# arduinoshield.net
KiCad netlist of a schematic drawn in Altium Designer
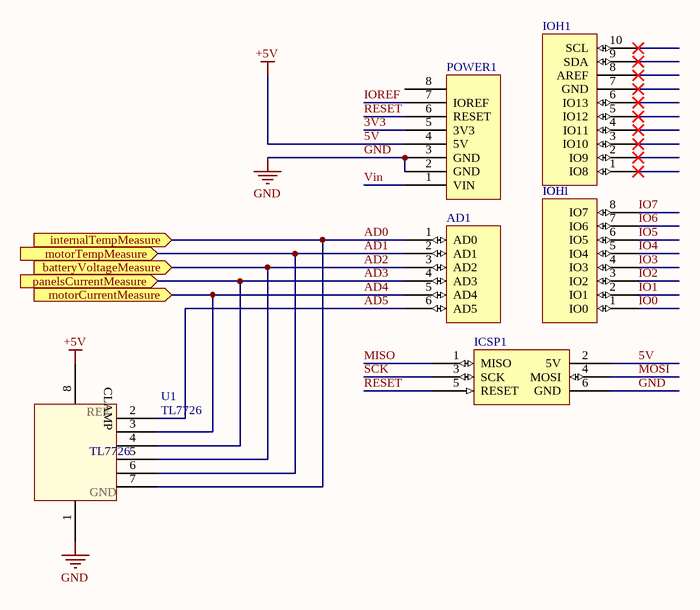
[diagram p0: arduinoshield.SchDoc]

(export (version "E")
  (design (tool "Eeschema 10.0.6"))
  (components
    (comp (ref "AD1")
      (value "AD")
      (footprint "Header:Header 6x1 8.5mm")
      (libsource (lib "Header") (part "AD"))
    )
    (comp (ref "ICSP1") (value "ICSP") (footprint "ICSP") (libsource (lib "Header") (part "ICSP")))
    (comp (ref "IOH1") (value "IOH") (footprint "Header 10x1 8.5mm") (libsource (lib "Header") (part "IOH")))
    (comp (ref "IOL1") (value "IOL") (footprint "Header 8x1 8.5mm") (libsource (lib "Header") (part "IOL")))
    (comp (ref "POWER1")
      (value "POWER_UNO")
      (footprint "Header 8x1 8.5mm")
      (libsource (lib "Header") (part "POWER_UNO"))
    )
    (comp (ref "U1")
      (value "TL7726")
      (footprint "DIP8-300")
      (description "Hex Clamping Circuit - Overvoltage Limiter")
      (libsource (lib "sensorsLib") (part "TL7726"))
    )
  )
  (nets
    (net (code "1") (name "+5V") (class "Default")
      (node (ref "ICSP1") (pin "2") (pinfunction "5V_2") (pintype "power_in"))
      (node (ref "POWER1") (pin "4") (pinfunction "5V_4") (pintype "power_in"))
      (node (ref "U1") (pin "8") (pinfunction "REF_8") (pintype "passive"))
    )
    (net (code "2") (name "/3V3") (class "Default")
      (node (ref "POWER1") (pin "5") (pinfunction "3V3_5") (pintype "power_in"))
    )
    (net (code "4") (name "/AD0") (class "Default")
      (node (ref "AD1") (pin "1") (pinfunction "AD0_1") (pintype "bidirectional"))
      (node (ref "U1") (pin "7") (pinfunction "CLAMP_7") (pintype "passive"))
    )
    (net (code "5") (name "/AD1") (class "Default")
      (node (ref "AD1") (pin "2") (pinfunction "AD1_2") (pintype "bidirectional"))
      (node (ref "U1") (pin "6") (pinfunction "CLAMP_6") (pintype "passive"))
    )
    (net (code "6") (name "/AD2") (class "Default")
      (node (ref "AD1") (pin "3") (pinfunction "AD2_3") (pintype "bidirectional"))
      (node (ref "U1") (pin "5") (pinfunction "CLAMP_5") (pintype "passive"))
    )
    (net (code "7") (name "/AD3") (class "Default")
      (node (ref "AD1") (pin "4") (pinfunction "AD3_4") (pintype "bidirectional"))
      (node (ref "U1") (pin "4") (pinfunction "CLAMP_4") (pintype "passive"))
    )
    (net (code "8") (name "/AD4") (class "Default")
      (node (ref "AD1") (pin "5") (pinfunction "AD4_5") (pintype "bidirectional"))
      (node (ref "U1") (pin "3") (pinfunction "CLAMP_3") (pintype "passive"))
    )
    (net (code "9") (name "/AD5") (class "Default")
      (node (ref "AD1") (pin "6") (pinfunction "AD5_6") (pintype "bidirectional"))
      (node (ref "U1") (pin "2") (pinfunction "CLAMP_2") (pintype "passive"))
    )
    (net (code "10") (name "/IO0") (class "Default")
      (node (ref "IOL1") (pin "1") (pinfunction "IO0_1") (pintype "bidirectional"))
    )
    (net (code "11") (name "/IO1") (class "Default")
      (node (ref "IOL1") (pin "2") (pinfunction "IO1_2") (pintype "bidirectional"))
    )
    (net (code "12") (name "/IO2") (class "Default")
      (node (ref "IOL1") (pin "3") (pinfunction "IO2_3") (pintype "bidirectional"))
    )
    (net (code "13") (name "/IO3") (class "Default")
      (node (ref "IOL1") (pin "4") (pinfunction "IO3_4") (pintype "bidirectional"))
    )
    (net (code "14") (name "/IO4") (class "Default")
      (node (ref "IOL1") (pin "5") (pinfunction "IO4_5") (pintype "bidirectional"))
    )
    (net (code "15") (name "/IO5") (class "Default")
      (node (ref "IOL1") (pin "6") (pinfunction "IO5_6") (pintype "bidirectional"))
    )
    (net (code "16") (name "/IO6") (class "Default")
      (node (ref "IOL1") (pin "7") (pinfunction "IO6_7") (pintype "bidirectional"))
    )
    (net (code "17") (name "/IO7") (class "Default")
      (node (ref "IOL1") (pin "8") (pinfunction "IO7_8") (pintype "bidirectional"))
    )
    (net (code "18") (name "/IOREF") (class "Default")
      (node (ref "POWER1") (pin "7") (pinfunction "IOREF_7") (pintype "power_in"))
    )
    (net (code "19") (name "/MISO") (class "Default")
      (node (ref "ICSP1") (pin "1") (pinfunction "MISO_1") (pintype "bidirectional"))
    )
    (net (code "20") (name "/MOSI") (class "Default")
      (node (ref "ICSP1") (pin "4") (pinfunction "MOSI_4") (pintype "bidirectional"))
    )
    (net (code "21") (name "/RESET") (class "Default")
      (node (ref "ICSP1") (pin "5") (pinfunction "RESET_5") (pintype "input"))
      (node (ref "POWER1") (pin "6") (pinfunction "RESET_6") (pintype "passive"))
    )
    (net (code "22") (name "/SCK") (class "Default")
      (node (ref "ICSP1") (pin "3") (pinfunction "SCK_3") (pintype "bidirectional"))
    )
    (net (code "23") (name "/Vin") (class "Default")
      (node (ref "POWER1") (pin "1") (pinfunction "VIN_1") (pintype "power_in"))
    )
    (net (code "24") (name "GND") (class "Default")
      (node (ref "ICSP1") (pin "6") (pinfunction "GND_6") (pintype "power_in"))
      (node (ref "POWER1") (pin "2") (pinfunction "GND_2") (pintype "power_in"))
      (node (ref "POWER1") (pin "3") (pinfunction "GND_3") (pintype "power_in"))
      (node (ref "U1") (pin "1") (pinfunction "GND_1") (pintype "passive"))
    )
    (net (code "25") (name "unconnected-(IOH1-AREF-Pad8)") (class "Default")
      (node (ref "IOH1") (pin "8") (pinfunction "AREF_8") (pintype "passive+no_connect"))
    )
    (net (code "26") (name "unconnected-(IOH1-GND-Pad7)") (class "Default")
      (node (ref "IOH1") (pin "7") (pinfunction "GND_7") (pintype "power_in+no_connect"))
    )
    (net (code "27") (name "unconnected-(IOH1-IO8-Pad1)") (class "Default")
      (node (ref "IOH1") (pin "1") (pinfunction "IO8_1") (pintype "bidirectional+no_connect"))
    )
    (net (code "28") (name "unconnected-(IOH1-IO9-Pad2)") (class "Default")
      (node (ref "IOH1") (pin "2") (pinfunction "IO9_2") (pintype "bidirectional+no_connect"))
    )
    (net (code "29") (name "unconnected-(IOH1-IO10-Pad3)") (class "Default")
      (node (ref "IOH1") (pin "3") (pinfunction "IO10_3") (pintype "bidirectional+no_connect"))
    )
    (net (code "30") (name "unconnected-(IOH1-IO11-Pad4)") (class "Default")
      (node (ref "IOH1") (pin "4") (pinfunction "IO11_4") (pintype "bidirectional+no_connect"))
    )
    (net (code "31") (name "unconnected-(IOH1-IO12-Pad5)") (class "Default")
      (node (ref "IOH1") (pin "5") (pinfunction "IO12_5") (pintype "bidirectional+no_connect"))
    )
    (net (code "32") (name "unconnected-(IOH1-IO13-Pad6)") (class "Default")
      (node (ref "IOH1") (pin "6") (pinfunction "IO13_6") (pintype "bidirectional+no_connect"))
    )
    (net (code "33") (name "unconnected-(IOH1-SCL-Pad10)") (class "Default")
      (node (ref "IOH1") (pin "10") (pinfunction "SCL_10") (pintype "bidirectional+no_connect"))
    )
    (net (code "34") (name "unconnected-(IOH1-SDA-Pad9)") (class "Default")
      (node (ref "IOH1") (pin "9") (pinfunction "SDA_9") (pintype "bidirectional+no_connect"))
    )
    (net (code "35") (name "unconnected-(POWER1-Pad8)") (class "Default")
      (node (ref "POWER1") (pin "8") (pintype "passive"))
    )
  )
)
